# MD_digital2.net
KiCad netlist of a schematic drawn in EAGLE
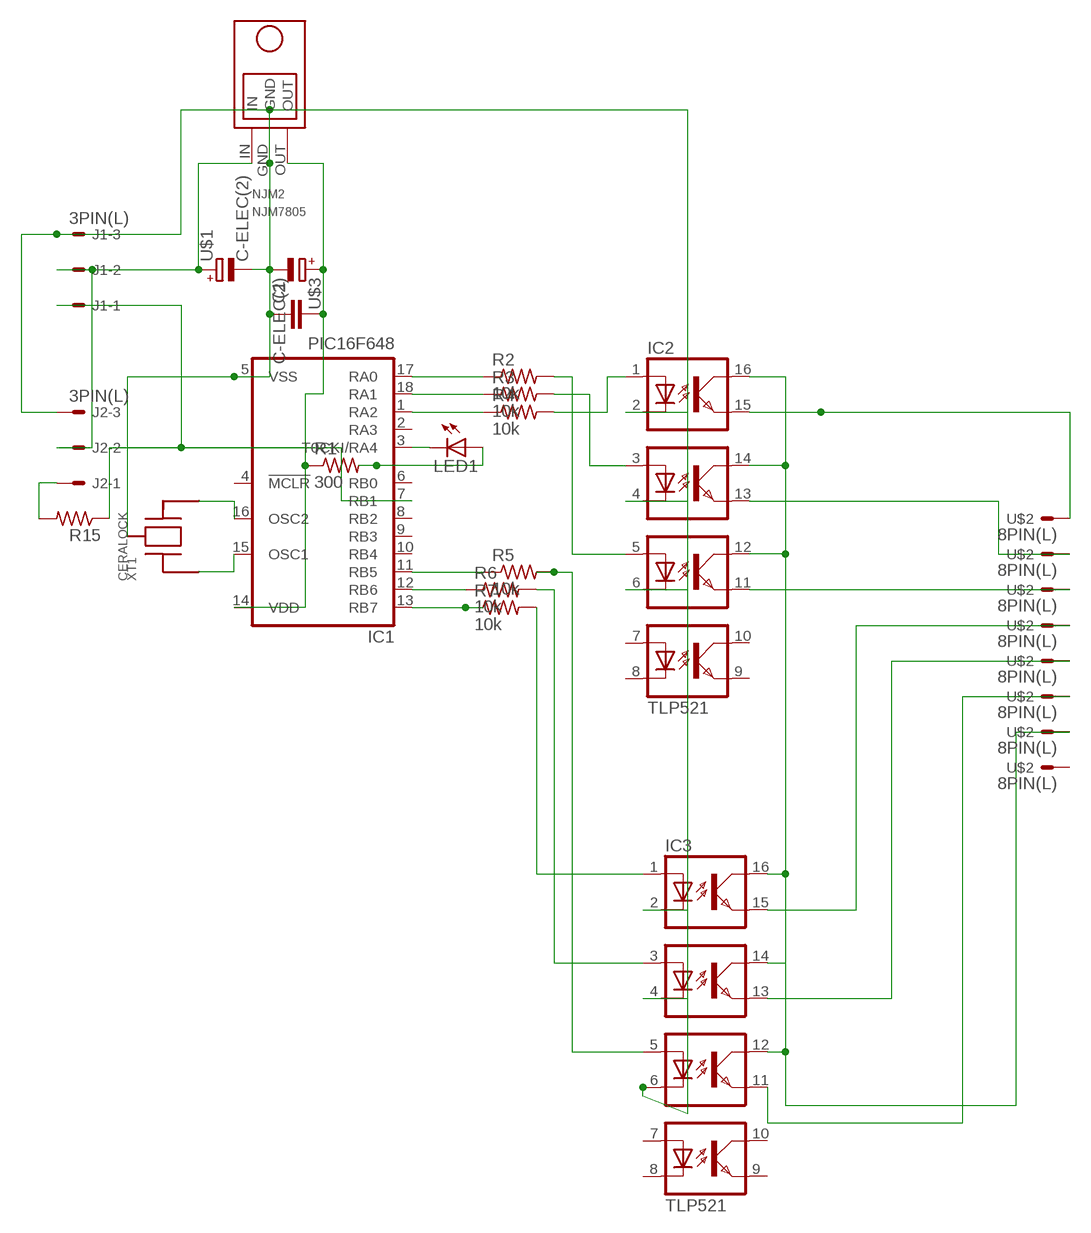
[diagram p0: schematic, sheet 1]

(export (version "E")
  (design (tool "Eeschema 10.0.6"))
  (components
    (comp (ref "C1")
      (value "C-")
      (footprint "eagle-import:C-2.54")
      (libsource (lib "eagle-import") (part "C-"))
    )
    (comp (ref "IC1")
      (value "PIC16F648")
      (footprint "eagle-import:DIL18")
      (libsource (lib "eagle-import") (part "PIC16F648"))
    )
    (comp (ref "IC2")
      (value "TLP521")
      (footprint "eagle-import:DIL16")
      (libsource (lib "eagle-import") (part "TLP521"))
    )
    (comp (ref "IC3")
      (value "TLP521")
      (footprint "eagle-import:DIL16")
      (libsource (lib "eagle-import") (part "TLP521"))
    )
    (comp (ref "J1")
      (value "3PIN(L)")
      (footprint "eagle-import:3PL")
      (libsource (lib "eagle-import") (part "3PIN(L)"))
    )
    (comp (ref "J2")
      (value "3PIN(L)")
      (footprint "eagle-import:3PL")
      (libsource (lib "eagle-import") (part "3PIN(L)"))
    )
    (comp (ref "LED1")
      (value "LED")
      (footprint "eagle-import:LED5MM")
      (libsource (lib "eagle-import") (part "LED"))
    )
    (comp (ref "NJM2")
      (value "NJM7805")
      (footprint "eagle-import:NJM7805")
      (libsource (lib "eagle-import") (part "NJM7805"))
    )
    (comp (ref "R1")
      (value "300")
      (footprint "eagle-import:0207_10")
      (libsource (lib "eagle-import") (part "R-"))
    )
    (comp (ref "R2")
      (value "10k")
      (footprint "eagle-import:0207_10")
      (libsource (lib "eagle-import") (part "R-"))
    )
    (comp (ref "R3")
      (value "10k")
      (footprint "eagle-import:0207_10")
      (libsource (lib "eagle-import") (part "R-"))
    )
    (comp (ref "R4")
      (value "10k")
      (footprint "eagle-import:0207_10")
      (libsource (lib "eagle-import") (part "R-"))
    )
    (comp (ref "R5")
      (value "10k")
      (footprint "eagle-import:0207_10")
      (libsource (lib "eagle-import") (part "R-"))
    )
    (comp (ref "R6")
      (value "10k")
      (footprint "eagle-import:0207_10")
      (libsource (lib "eagle-import") (part "R-"))
    )
    (comp (ref "R7")
      (value "10k")
      (footprint "eagle-import:0207_10")
      (libsource (lib "eagle-import") (part "R-"))
    )
    (comp (ref "R15")
      (value "R-")
      (footprint "eagle-import:0207_10")
      (libsource (lib "eagle-import") (part "R-"))
    )
    (comp (ref "U$1")
      (value "C-ELEC(2)")
      (footprint "eagle-import:C-6MM(2)")
      (libsource (lib "eagle-import") (part "C-ELEC(2)"))
    )
    (comp (ref "U$2")
      (value "8PIN(L)")
      (footprint "eagle-import:8PL")
      (libsource (lib "eagle-import") (part "8PIN(L)"))
    )
    (comp (ref "U$3")
      (value "C-ELEC(2)")
      (footprint "eagle-import:C-6MM(2)")
      (libsource (lib "eagle-import") (part "C-ELEC(2)"))
    )
    (comp (ref "XT1")
      (value "CERALOCK")
      (footprint "eagle-import:CERALOCK")
      (libsource (lib "eagle-import") (part "CERALOCK"))
    )
  )
  (nets
    (net (code "1") (name "Net-(C1-1)") (class "Default")
      (node (ref "C1") (pin "P$1") (pinfunction "1_P$1") (pintype "passive"))
      (node (ref "IC1") (pin "5") (pinfunction "VSS_5") (pintype "power_in"))
      (node (ref "IC2") (pin "2") (pinfunction "C0_2") (pintype "passive"))
      (node (ref "IC2") (pin "4") (pinfunction "C1_4") (pintype "passive"))
      (node (ref "IC2") (pin "6") (pinfunction "C2_6") (pintype "passive"))
      (node (ref "IC3") (pin "2") (pinfunction "C0_2") (pintype "passive"))
      (node (ref "IC3") (pin "4") (pinfunction "C1_4") (pintype "passive"))
      (node (ref "IC3") (pin "6") (pinfunction "C2_6") (pintype "passive"))
      (node (ref "J1") (pin "3") (pinfunction "S_3") (pintype "passive"))
      (node (ref "J2") (pin "3") (pinfunction "S_3") (pintype "passive"))
      (node (ref "NJM2") (pin "GND") (pinfunction "GND_GND") (pintype "bidirectional"))
      (node (ref "U$1") (pin "-") (pinfunction "-_-") (pintype "passive"))
      (node (ref "U$3") (pin "-") (pinfunction "-_-") (pintype "passive"))
      (node (ref "XT1") (pin "P2") (pinfunction "2_P2") (pintype "passive"))
    )
    (net (code "2") (name "Net-(C1-2)") (class "Default")
      (node (ref "C1") (pin "P$2") (pinfunction "2_P$2") (pintype "passive"))
      (node (ref "IC1") (pin "14") (pinfunction "VDD_14") (pintype "power_in"))
      (node (ref "NJM2") (pin "OUT") (pinfunction "OUT_OUT") (pintype "bidirectional"))
      (node (ref "R1") (pin "1") (pinfunction "1_1") (pintype "passive"))
      (node (ref "U$3") (pin "+") (pinfunction "+_+") (pintype "passive"))
    )
    (net (code "3") (name "Net-(IC1-OSC1)") (class "Default")
      (node (ref "IC1") (pin "15") (pinfunction "OSC1_15") (pintype "input"))
      (node (ref "XT1") (pin "P1") (pinfunction "1_P1") (pintype "passive"))
    )
    (net (code "4") (name "Net-(IC1-OSC2)") (class "Default")
      (node (ref "IC1") (pin "16") (pinfunction "OSC2_16") (pintype "output"))
      (node (ref "XT1") (pin "P3") (pinfunction "3_P3") (pintype "passive"))
    )
    (net (code "5") (name "Net-(IC1-RA0)") (class "Default")
      (node (ref "IC1") (pin "17") (pinfunction "RA0_17") (pintype "bidirectional"))
      (node (ref "R2") (pin "1") (pinfunction "1_1") (pintype "passive"))
    )
    (net (code "6") (name "Net-(IC1-RA1)") (class "Default")
      (node (ref "IC1") (pin "18") (pinfunction "RA1_18") (pintype "bidirectional"))
      (node (ref "R3") (pin "1") (pinfunction "1_1") (pintype "passive"))
    )
    (net (code "7") (name "Net-(IC1-RA2)") (class "Default")
      (node (ref "IC1") (pin "1") (pinfunction "RA2_1") (pintype "bidirectional"))
      (node (ref "R4") (pin "1") (pinfunction "1_1") (pintype "passive"))
    )
    (net (code "8") (name "Net-(IC1-RB1)") (class "Default")
      (node (ref "IC1") (pin "7") (pinfunction "RB1_7") (pintype "bidirectional"))
      (node (ref "J1") (pin "1") (pinfunction "S_1") (pintype "passive"))
      (node (ref "R15") (pin "1") (pinfunction "1_1") (pintype "passive"))
    )
    (net (code "9") (name "Net-(IC1-RB5)") (class "Default")
      (node (ref "IC1") (pin "11") (pinfunction "RB5_11") (pintype "bidirectional"))
      (node (ref "R5") (pin "1") (pinfunction "1_1") (pintype "passive"))
    )
    (net (code "10") (name "Net-(IC1-RB6)") (class "Default")
      (node (ref "IC1") (pin "12") (pinfunction "RB6_12") (pintype "bidirectional"))
      (node (ref "R6") (pin "1") (pinfunction "1_1") (pintype "passive"))
    )
    (net (code "11") (name "Net-(IC1-RB7)") (class "Default")
      (node (ref "IC1") (pin "13") (pinfunction "RB7_13") (pintype "bidirectional"))
      (node (ref "R7") (pin "1") (pinfunction "1_1") (pintype "passive"))
    )
    (net (code "12") (name "Net-(IC1-T0CKI{slash}RA4)") (class "Default")
      (node (ref "IC1") (pin "3") (pinfunction "T0CKI/RA4_3") (pintype "bidirectional"))
      (node (ref "LED1") (pin "K") (pinfunction "C_K") (pintype "passive"))
    )
    (net (code "13") (name "Net-(IC2-A0)") (class "Default")
      (node (ref "IC2") (pin "1") (pinfunction "A0_1") (pintype "passive"))
      (node (ref "R4") (pin "2") (pinfunction "2_2") (pintype "passive"))
    )
    (net (code "14") (name "Net-(IC2-A1)") (class "Default")
      (node (ref "IC2") (pin "3") (pinfunction "A1_3") (pintype "passive"))
      (node (ref "R3") (pin "2") (pinfunction "2_2") (pintype "passive"))
    )
    (net (code "15") (name "Net-(IC2-A2)") (class "Default")
      (node (ref "IC2") (pin "5") (pinfunction "A2_5") (pintype "passive"))
      (node (ref "R2") (pin "2") (pinfunction "2_2") (pintype "passive"))
    )
    (net (code "16") (name "Net-(IC2-COL0)") (class "Default")
      (node (ref "IC2") (pin "12") (pinfunction "COL2_12") (pintype "passive"))
      (node (ref "IC2") (pin "14") (pinfunction "COL1_14") (pintype "passive"))
      (node (ref "IC2") (pin "16") (pinfunction "COL0_16") (pintype "passive"))
      (node (ref "IC3") (pin "12") (pinfunction "COL2_12") (pintype "passive"))
      (node (ref "IC3") (pin "14") (pinfunction "COL1_14") (pintype "passive"))
      (node (ref "IC3") (pin "16") (pinfunction "COL0_16") (pintype "passive"))
      (node (ref "U$2") (pin "P7") (pinfunction "P7_P7") (pintype "passive"))
    )
    (net (code "17") (name "Net-(IC2-EMIT0)") (class "Default")
      (node (ref "IC2") (pin "15") (pinfunction "EMIT0_15") (pintype "passive"))
      (node (ref "U$2") (pin "P1") (pinfunction "P1_P1") (pintype "passive"))
    )
    (net (code "18") (name "Net-(IC2-EMIT1)") (class "Default")
      (node (ref "IC2") (pin "13") (pinfunction "EMIT1_13") (pintype "passive"))
      (node (ref "U$2") (pin "P2") (pinfunction "P2_P2") (pintype "passive"))
    )
    (net (code "19") (name "Net-(IC2-EMIT2)") (class "Default")
      (node (ref "IC2") (pin "11") (pinfunction "EMIT2_11") (pintype "passive"))
      (node (ref "U$2") (pin "P3") (pinfunction "P3_P3") (pintype "passive"))
    )
    (net (code "20") (name "Net-(IC3-A0)") (class "Default")
      (node (ref "IC3") (pin "1") (pinfunction "A0_1") (pintype "passive"))
      (node (ref "R7") (pin "2") (pinfunction "2_2") (pintype "passive"))
    )
    (net (code "21") (name "Net-(IC3-A1)") (class "Default")
      (node (ref "IC3") (pin "3") (pinfunction "A1_3") (pintype "passive"))
      (node (ref "R6") (pin "2") (pinfunction "2_2") (pintype "passive"))
    )
    (net (code "22") (name "Net-(IC3-A2)") (class "Default")
      (node (ref "IC3") (pin "5") (pinfunction "A2_5") (pintype "passive"))
      (node (ref "R5") (pin "2") (pinfunction "2_2") (pintype "passive"))
    )
    (net (code "23") (name "Net-(IC3-EMIT0)") (class "Default")
      (node (ref "IC3") (pin "15") (pinfunction "EMIT0_15") (pintype "passive"))
      (node (ref "U$2") (pin "P4") (pinfunction "P4_P4") (pintype "passive"))
    )
    (net (code "24") (name "Net-(IC3-EMIT1)") (class "Default")
      (node (ref "IC3") (pin "13") (pinfunction "EMIT1_13") (pintype "passive"))
      (node (ref "U$2") (pin "P5") (pinfunction "P5_P5") (pintype "passive"))
    )
    (net (code "25") (name "Net-(IC3-EMIT2)") (class "Default")
      (node (ref "IC3") (pin "11") (pinfunction "EMIT2_11") (pintype "passive"))
      (node (ref "U$2") (pin "P6") (pinfunction "P6_P6") (pintype "passive"))
    )
    (net (code "26") (name "Net-(J1B-S)") (class "Default")
      (node (ref "J1") (pin "2") (pinfunction "S_2") (pintype "passive"))
      (node (ref "J2") (pin "2") (pinfunction "S_2") (pintype "passive"))
      (node (ref "NJM2") (pin "IN") (pinfunction "IN_IN") (pintype "bidirectional"))
      (node (ref "U$1") (pin "+") (pinfunction "+_+") (pintype "passive"))
    )
    (net (code "27") (name "Net-(J2A-S)") (class "Default")
      (node (ref "J2") (pin "1") (pinfunction "S_1") (pintype "passive"))
      (node (ref "R15") (pin "2") (pinfunction "2_2") (pintype "passive"))
    )
    (net (code "28") (name "Net-(LED1-PadA)") (class "Default")
      (node (ref "LED1") (pin "A") (pinfunction "A_A") (pintype "passive"))
      (node (ref "R1") (pin "2") (pinfunction "2_2") (pintype "passive"))
    )
    (net (code "29") (name "unconnected-(IC1-RA3-Pad2)") (class "Default")
      (node (ref "IC1") (pin "2") (pinfunction "RA3_2") (pintype "bidirectional"))
    )
    (net (code "30") (name "unconnected-(IC1-RB0-Pad6)") (class "Default")
      (node (ref "IC1") (pin "6") (pinfunction "RB0_6") (pintype "bidirectional"))
    )
    (net (code "31") (name "unconnected-(IC1-RB2-Pad8)") (class "Default")
      (node (ref "IC1") (pin "8") (pinfunction "RB2_8") (pintype "bidirectional"))
    )
    (net (code "32") (name "unconnected-(IC1-RB3-Pad9)") (class "Default")
      (node (ref "IC1") (pin "9") (pinfunction "RB3_9") (pintype "bidirectional"))
    )
    (net (code "33") (name "unconnected-(IC1-RB4-Pad10)") (class "Default")
      (node (ref "IC1") (pin "10") (pinfunction "RB4_10") (pintype "bidirectional"))
    )
    (net (code "34") (name "unconnected-(IC1-~{MCLR}-Pad4)") (class "Default")
      (node (ref "IC1") (pin "4") (pinfunction "~{MCLR}_4") (pintype "input"))
    )
    (net (code "35") (name "unconnected-(IC2-A3-Pad7)") (class "Default")
      (node (ref "IC2") (pin "7") (pinfunction "A3_7") (pintype "passive"))
    )
    (net (code "36") (name "unconnected-(IC2-C3-Pad8)") (class "Default")
      (node (ref "IC2") (pin "8") (pinfunction "C3_8") (pintype "passive"))
    )
    (net (code "37") (name "unconnected-(IC2-COL3-Pad10)") (class "Default")
      (node (ref "IC2") (pin "10") (pinfunction "COL3_10") (pintype "passive"))
    )
    (net (code "38") (name "unconnected-(IC2-EMIT3-Pad9)") (class "Default")
      (node (ref "IC2") (pin "9") (pinfunction "EMIT3_9") (pintype "passive"))
    )
    (net (code "39") (name "unconnected-(IC3-A3-Pad7)") (class "Default")
      (node (ref "IC3") (pin "7") (pinfunction "A3_7") (pintype "passive"))
    )
    (net (code "40") (name "unconnected-(IC3-C3-Pad8)") (class "Default")
      (node (ref "IC3") (pin "8") (pinfunction "C3_8") (pintype "passive"))
    )
    (net (code "41") (name "unconnected-(IC3-COL3-Pad10)") (class "Default")
      (node (ref "IC3") (pin "10") (pinfunction "COL3_10") (pintype "passive"))
    )
    (net (code "42") (name "unconnected-(IC3-EMIT3-Pad9)") (class "Default")
      (node (ref "IC3") (pin "9") (pinfunction "EMIT3_9") (pintype "passive"))
    )
    (net (code "43") (name "unconnected-(U$2-PadP8)") (class "Default")
      (node (ref "U$2") (pin "P8") (pinfunction "P8_P8") (pintype "passive"))
    )
  )
)
